# MRCS-BBProMini.net
KiCad netlist of a schematic drawn in EAGLE
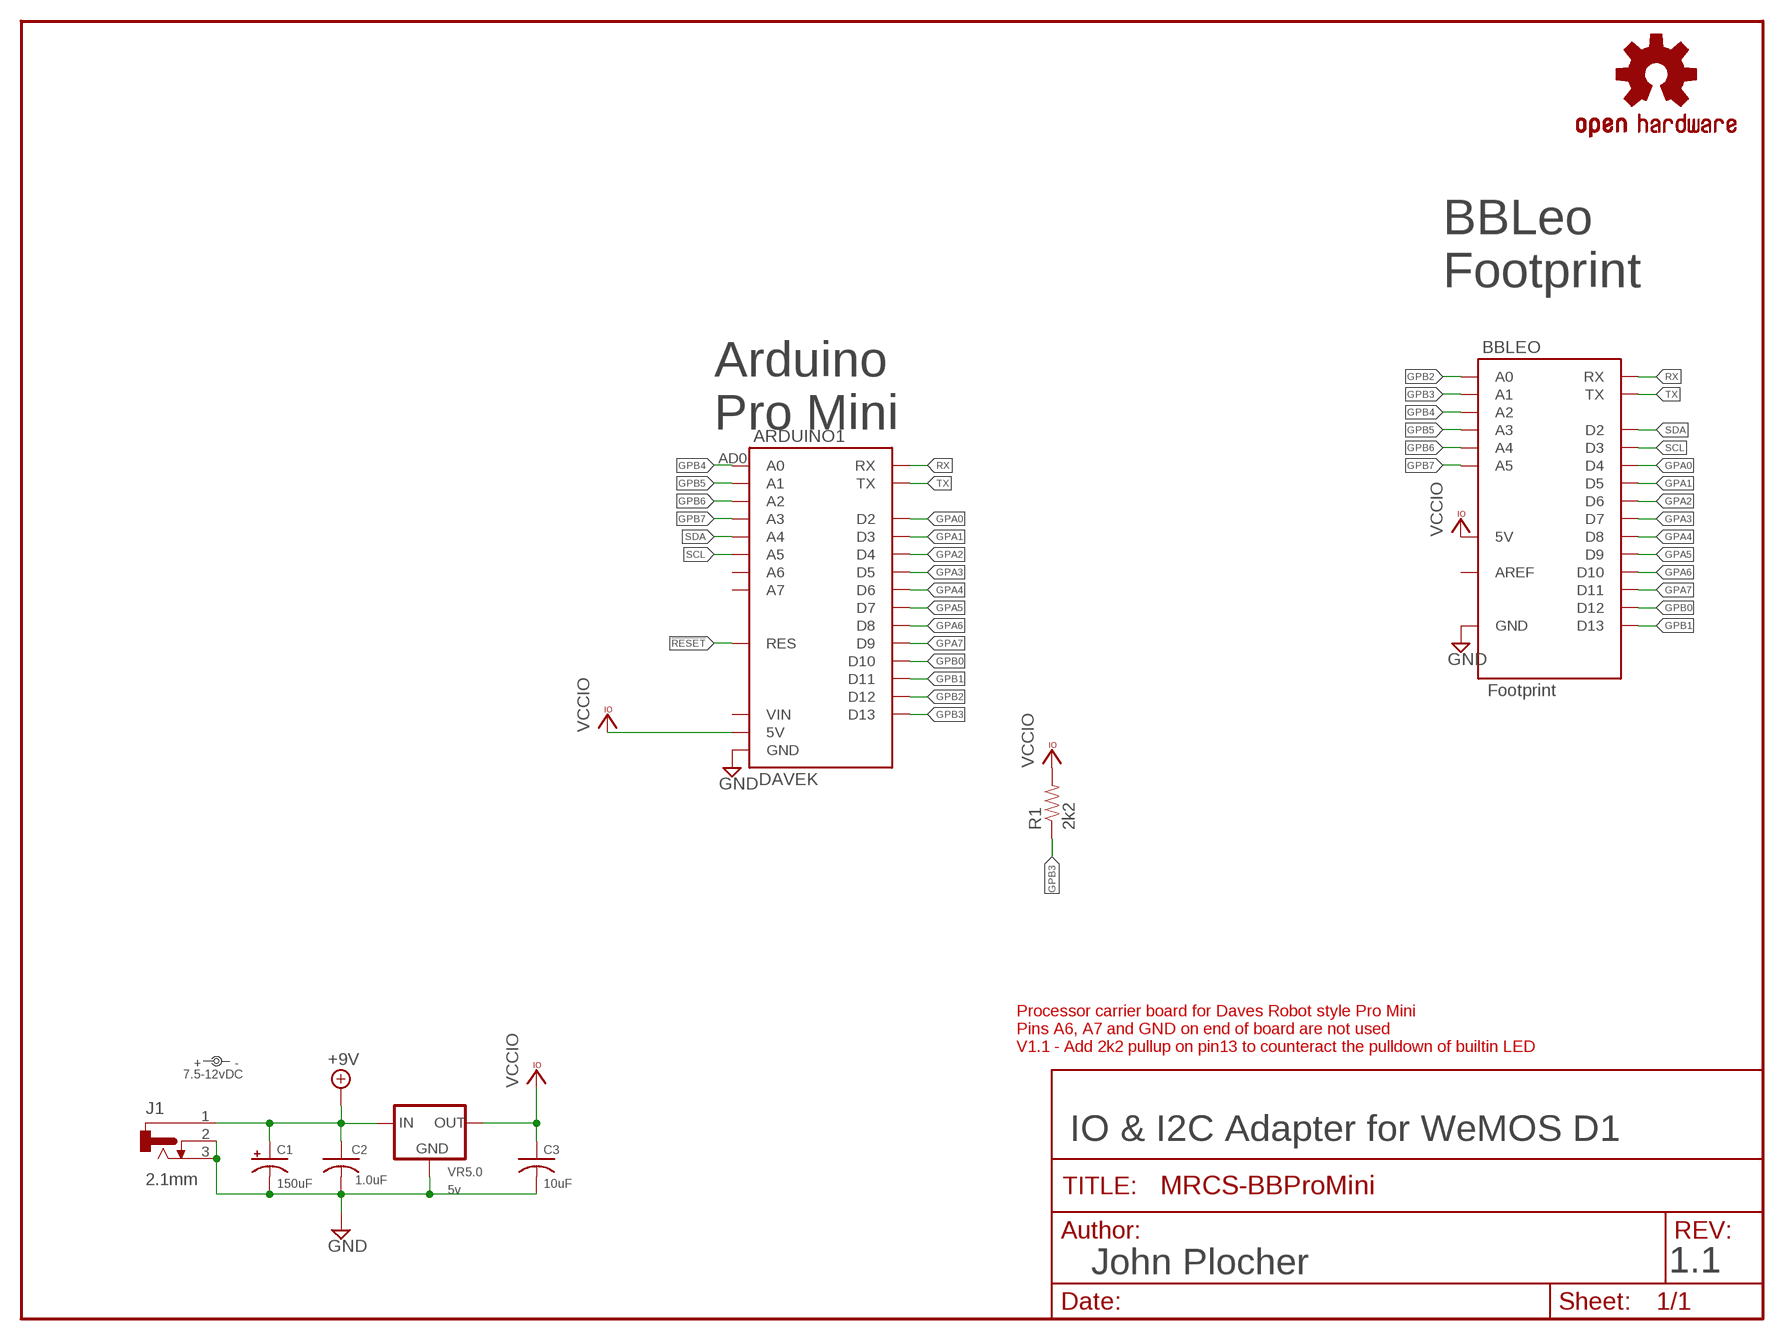
[diagram p0: schematic, sheet 1]

(export (version "E")
  (design (tool "Eeschema 10.0.6"))
  (components
    (comp (ref "ARDUINO1")
      (value "DAVEK")
      (footprint "eagle-import:ARDUINO_PRO_MINI_DAVEK")
      (libsource (lib "eagle-import") (part "ARDUINO-PRO-MINIDAVESROBOT"))
    )
    (comp (ref "BBLEO")
      (value "Footprint")
      (footprint "eagle-import:ARDUINO-BBLEO")
      (libsource (lib "eagle-import") (part "ARDUINO-BBLEO"))
    )
    (comp (ref "C1")
      (value "150uF")
      (footprint "eagle-import:E5-10.5")
      (libsource (lib "eagle-import") (part "CAP-POLPTH-5MM"))
    )
    (comp (ref "C2")
      (value "1.0uF")
      (footprint "eagle-import:C050-024X044")
      (libsource (lib "eagle-import") (part "CAPPTH1"))
    )
    (comp (ref "C3")
      (value "10uF")
      (footprint "eagle-import:C050-024X044")
      (libsource (lib "eagle-import") (part "CAPPTH1"))
    )
    (comp (ref "J1")
      (value "2.1mm")
      (footprint "eagle-import:DCJ0202")
      (libsource (lib "eagle-import") (part "CONNECTOR-DC-POWER-RA"))
    )
    (comp (ref "LABEL1")
      (value "7.5-12vDC")
      (footprint "eagle-import:PWR_LABEL")
      (libsource (lib "eagle-import") (part "DOC-POWER_LABEL"))
    )
    (comp (ref "OSHW1")
      (value "OSHW")
      (footprint "eagle-import:OSHW-LOGO-M")
      (libsource (lib "eagle-import") (part "DOC-OSHW-LOGO-M"))
    )
    (comp (ref "R1")
      (value "2k2")
      (footprint "eagle-import:AXIAL-0.3-RES")
      (libsource (lib "eagle-import") (part "RPTH03"))
    )
    (comp (ref "VR5.0")
      (value "5v")
      (footprint "eagle-import:TO-220-RA")
      (libsource (lib "eagle-import") (part "VREG-?-PTH-RA"))
    )
  )
  (nets
    (net (code "1") (name "+9V") (class "Default")
      (node (ref "C1") (pin "+") (pinfunction "+_+") (pintype "passive"))
      (node (ref "C2") (pin "1") (pinfunction "1_1") (pintype "passive"))
      (node (ref "J1") (pin "1") (pinfunction "1_1") (pintype "passive"))
      (node (ref "VR5.0") (pin "IN") (pinfunction "IN_IN") (pintype "input"))
    )
    (net (code "2") (name "/~{RESET}") (class "Default")
      (node (ref "ARDUINO1") (pin "RES") (pinfunction "RES_RES") (pintype "bidirectional"))
      (node (ref "ARDUINO1") (pin "RES@1") (pinfunction "RES_RES@1") (pintype "bidirectional"))
    )
    (net (code "3") (name "GND") (class "Default")
      (node (ref "ARDUINO1") (pin "GND@1") (pinfunction "GND_GND@1") (pintype "bidirectional"))
      (node (ref "ARDUINO1") (pin "GND@2") (pinfunction "GND_GND@2") (pintype "bidirectional"))
      (node (ref "ARDUINO1") (pin "GND@4") (pinfunction "GND_GND@4") (pintype "bidirectional"))
      (node (ref "BBLEO") (pin "GND@0") (pinfunction "GND_GND@0") (pintype "bidirectional"))
      (node (ref "BBLEO") (pin "GND@1") (pinfunction "GND_GND@1") (pintype "bidirectional"))
      (node (ref "BBLEO") (pin "GND@2") (pinfunction "GND_GND@2") (pintype "bidirectional"))
      (node (ref "BBLEO") (pin "GND@3") (pinfunction "GND_GND@3") (pintype "bidirectional"))
      (node (ref "BBLEO") (pin "GND@4") (pinfunction "GND_GND@4") (pintype "bidirectional"))
      (node (ref "C1") (pin "-") (pinfunction "-_-") (pintype "passive"))
      (node (ref "C2") (pin "2") (pinfunction "2_2") (pintype "passive"))
      (node (ref "C3") (pin "2") (pinfunction "2_2") (pintype "passive"))
      (node (ref "J1") (pin "2") (pinfunction "2_2") (pintype "passive"))
      (node (ref "J1") (pin "3") (pinfunction "3_3") (pintype "passive"))
      (node (ref "VR5.0") (pin "GND") (pinfunction "GND_GND") (pintype "input"))
    )
    (net (code "4") (name "GPA0") (class "Default")
      (node (ref "ARDUINO1") (pin "D2") (pinfunction "D2_D2") (pintype "bidirectional"))
      (node (ref "BBLEO") (pin "D4") (pinfunction "D4_D4") (pintype "bidirectional"))
    )
    (net (code "5") (name "GPA1") (class "Default")
      (node (ref "ARDUINO1") (pin "D3") (pinfunction "D3_D3") (pintype "bidirectional"))
      (node (ref "BBLEO") (pin "D5") (pinfunction "D5_D5") (pintype "bidirectional"))
    )
    (net (code "6") (name "GPA2") (class "Default")
      (node (ref "ARDUINO1") (pin "D4") (pinfunction "D4_D4") (pintype "bidirectional"))
      (node (ref "BBLEO") (pin "D6") (pinfunction "D6_D6") (pintype "bidirectional"))
    )
    (net (code "7") (name "GPA3") (class "Default")
      (node (ref "ARDUINO1") (pin "D5") (pinfunction "D5_D5") (pintype "bidirectional"))
      (node (ref "BBLEO") (pin "D7") (pinfunction "D7_D7") (pintype "bidirectional"))
    )
    (net (code "8") (name "GPA4") (class "Default")
      (node (ref "ARDUINO1") (pin "D6") (pinfunction "D6_D6") (pintype "bidirectional"))
      (node (ref "BBLEO") (pin "D8") (pinfunction "D8_D8") (pintype "bidirectional"))
    )
    (net (code "9") (name "GPA5") (class "Default")
      (node (ref "ARDUINO1") (pin "D7") (pinfunction "D7_D7") (pintype "bidirectional"))
      (node (ref "BBLEO") (pin "D9") (pinfunction "D9_D9") (pintype "bidirectional"))
    )
    (net (code "10") (name "GPA6") (class "Default")
      (node (ref "ARDUINO1") (pin "D8") (pinfunction "D8_D8") (pintype "bidirectional"))
      (node (ref "BBLEO") (pin "D10") (pinfunction "D10_D10") (pintype "bidirectional"))
    )
    (net (code "11") (name "GPA7") (class "Default")
      (node (ref "ARDUINO1") (pin "D9") (pinfunction "D9_D9") (pintype "bidirectional"))
      (node (ref "BBLEO") (pin "D11") (pinfunction "D11_D11") (pintype "bidirectional"))
    )
    (net (code "12") (name "GPB0") (class "Default")
      (node (ref "ARDUINO1") (pin "D10") (pinfunction "D10_D10") (pintype "bidirectional"))
      (node (ref "BBLEO") (pin "D12") (pinfunction "D12_D12") (pintype "bidirectional"))
    )
    (net (code "13") (name "GPB1") (class "Default")
      (node (ref "ARDUINO1") (pin "D11") (pinfunction "D11_D11") (pintype "bidirectional"))
      (node (ref "BBLEO") (pin "D13") (pinfunction "D13_D13") (pintype "bidirectional"))
    )
    (net (code "14") (name "GPB2") (class "Default")
      (node (ref "ARDUINO1") (pin "D12") (pinfunction "D12_D12") (pintype "bidirectional"))
      (node (ref "BBLEO") (pin "A0") (pinfunction "A0_A0") (pintype "bidirectional"))
    )
    (net (code "15") (name "GPB3") (class "Default")
      (node (ref "ARDUINO1") (pin "D13") (pinfunction "D13_D13") (pintype "bidirectional"))
      (node (ref "BBLEO") (pin "A1") (pinfunction "A1_A1") (pintype "bidirectional"))
      (node (ref "R1") (pin "P$1") (pinfunction "1_P$1") (pintype "passive"))
    )
    (net (code "16") (name "GPB4") (class "Default")
      (node (ref "ARDUINO1") (pin "AD0") (pinfunction "A0_AD0") (pintype "bidirectional"))
      (node (ref "BBLEO") (pin "A2") (pinfunction "A2_A2") (pintype "bidirectional"))
    )
    (net (code "17") (name "GPB5") (class "Default")
      (node (ref "ARDUINO1") (pin "AD1") (pinfunction "A1_AD1") (pintype "bidirectional"))
      (node (ref "BBLEO") (pin "A3") (pinfunction "A3_A3") (pintype "bidirectional"))
    )
    (net (code "18") (name "GPB6") (class "Default")
      (node (ref "ARDUINO1") (pin "AD2") (pinfunction "A2_AD2") (pintype "bidirectional"))
      (node (ref "BBLEO") (pin "A4") (pinfunction "A4_A4") (pintype "bidirectional"))
    )
    (net (code "19") (name "GPB7") (class "Default")
      (node (ref "ARDUINO1") (pin "AD3") (pinfunction "A3_AD3") (pintype "bidirectional"))
      (node (ref "BBLEO") (pin "A5") (pinfunction "A5_A5") (pintype "bidirectional"))
    )
    (net (code "20") (name "RX") (class "Default")
      (node (ref "ARDUINO1") (pin "RX") (pinfunction "RX_RX") (pintype "bidirectional"))
      (node (ref "BBLEO") (pin "RX") (pinfunction "RX_RX") (pintype "bidirectional"))
    )
    (net (code "21") (name "SCL") (class "Default")
      (node (ref "ARDUINO1") (pin "AD5") (pinfunction "A5_AD5") (pintype "bidirectional"))
      (node (ref "BBLEO") (pin "SCL") (pinfunction "D3_SCL") (pintype "bidirectional"))
    )
    (net (code "22") (name "SDA") (class "Default")
      (node (ref "ARDUINO1") (pin "AD4") (pinfunction "A4_AD4") (pintype "bidirectional"))
      (node (ref "BBLEO") (pin "SDA") (pinfunction "D2_SDA") (pintype "bidirectional"))
    )
    (net (code "23") (name "TX") (class "Default")
      (node (ref "ARDUINO1") (pin "TX@1") (pinfunction "TX_TX@1") (pintype "bidirectional"))
      (node (ref "BBLEO") (pin "TX") (pinfunction "TX_TX") (pintype "bidirectional"))
    )
    (net (code "24") (name "VCCIO") (class "Default")
      (node (ref "ARDUINO1") (pin "5V") (pinfunction "5V_5V") (pintype "bidirectional"))
      (node (ref "BBLEO") (pin "+5V@1") (pinfunction "5V_+5V@1") (pintype "bidirectional"))
      (node (ref "BBLEO") (pin "+5V@2") (pinfunction "5V_+5V@2") (pintype "bidirectional"))
      (node (ref "BBLEO") (pin "+5V@3") (pinfunction "5V_+5V@3") (pintype "bidirectional"))
      (node (ref "BBLEO") (pin "+5V@4") (pinfunction "5V_+5V@4") (pintype "bidirectional"))
      (node (ref "C3") (pin "1") (pinfunction "1_1") (pintype "passive"))
      (node (ref "R1") (pin "P$2") (pinfunction "2_P$2") (pintype "passive"))
      (node (ref "VR5.0") (pin "OUT") (pinfunction "OUT_OUT") (pintype "output"))
    )
    (net (code "25") (name "unconnected-(ARDUINO1-A6-PadAD6)") (class "Default")
      (node (ref "ARDUINO1") (pin "AD6") (pinfunction "A6_AD6") (pintype "bidirectional"))
    )
    (net (code "26") (name "unconnected-(ARDUINO1-A7-PadAD7)") (class "Default")
      (node (ref "ARDUINO1") (pin "AD7") (pinfunction "A7_AD7") (pintype "bidirectional"))
    )
    (net (code "27") (name "unconnected-(ARDUINO1-PadVIN)") (class "Default")
      (node (ref "ARDUINO1") (pin "VIN") (pinfunction "VIN_VIN") (pintype "bidirectional"))
    )
    (net (code "28") (name "unconnected-(BBLEO-AREF-PadAR)") (class "Default")
      (node (ref "BBLEO") (pin "AR") (pinfunction "AREF_AR") (pintype "bidirectional"))
    )
  )
)
